# Lights.net
KiCad netlist of a schematic drawn in Altium Designer
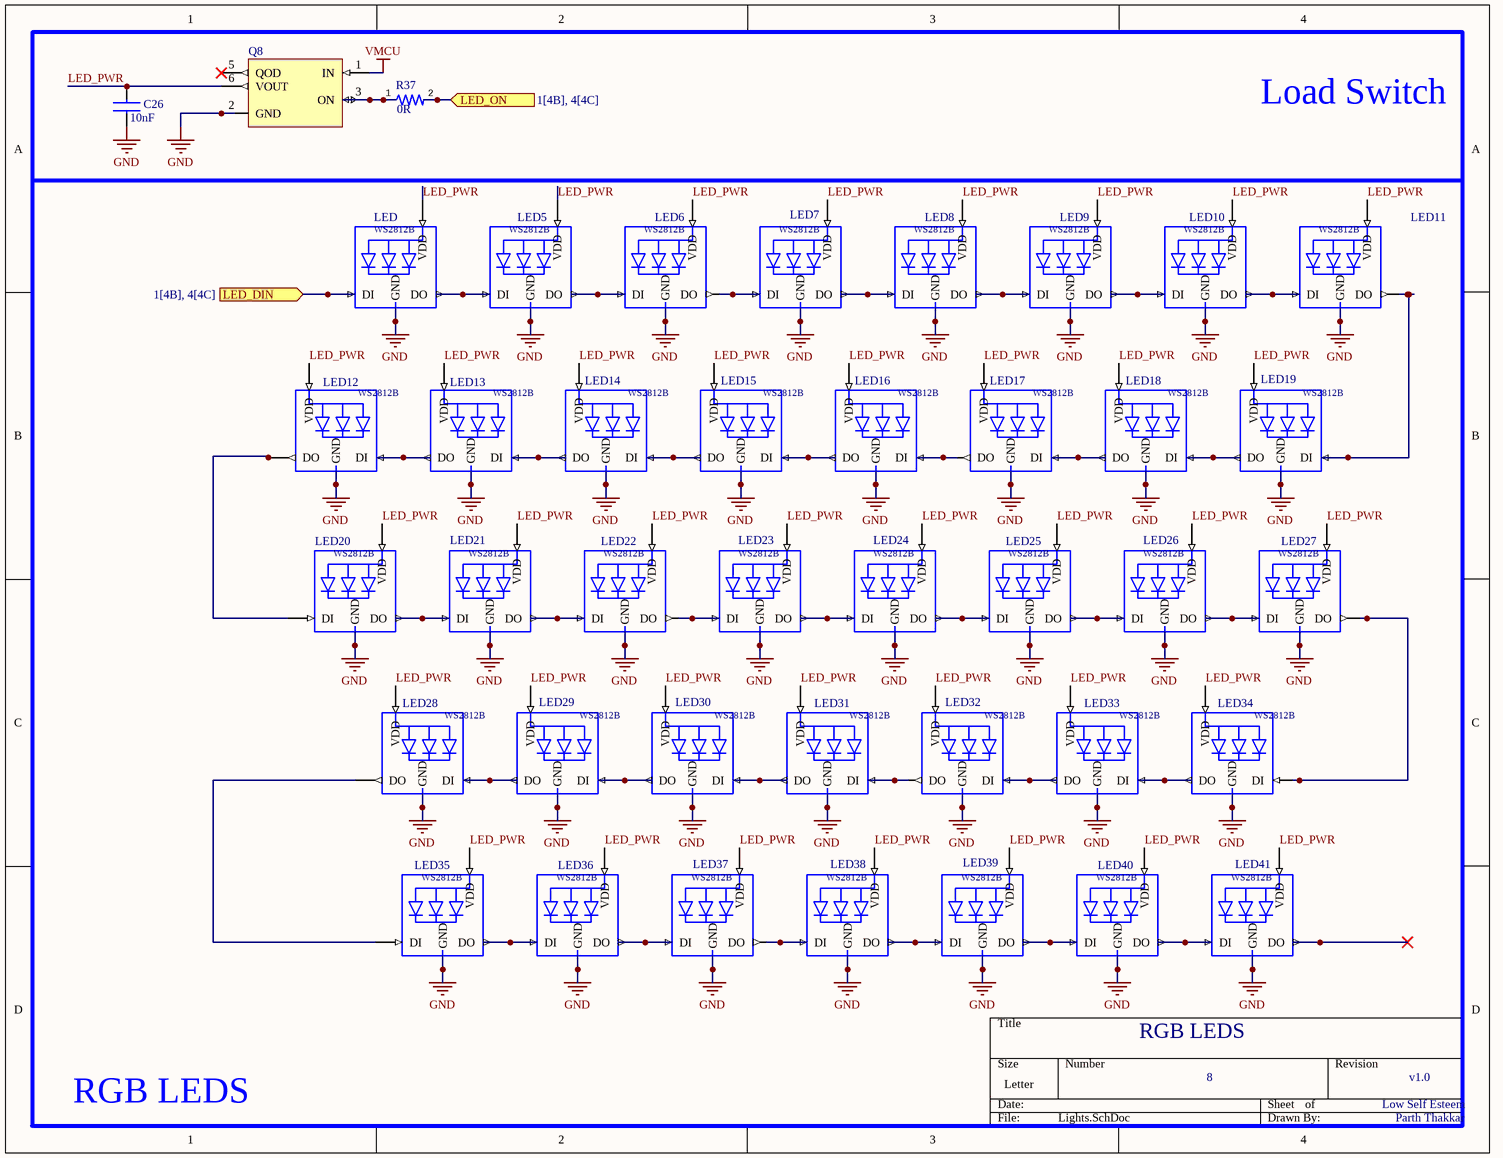
[diagram p0: Lights.SchDoc]

(export (version "E")
  (design (tool "Eeschema 10.0.6"))
  (components
    (comp (ref "C26")
      (value "10nF")
      (footprint "Capacitor 0603")
      (fields
        (field (name "MANUFACTURER") "Murata")
        (field (name "MANUFACTURER PART NUMBER") "GCM188R72A103KA37D")
        (field (name "Comment") "CAP 0.1uF 100V 0603")
      )
      (libsource (lib "InsaneIntegratedLib") (part "CAP 0.1uF 100V 0603"))
    )
    (comp (ref "LED")
      (value "WS2812B")
      (footprint "WS2812B")
      (description "Raspberry Pi HAT _40 pin_ Wheeled Robotics Kit")
      (fields (field (name "MF") "SparkFun Electronics"))
      (libsource (lib "Keyboard_parts") (part "WS2812B"))
    )
    (comp (ref "LED5")
      (value "WS2812B")
      (footprint "WS2812B")
      (description "Raspberry Pi HAT _40 pin_ Wheeled Robotics Kit")
      (fields (field (name "MF") "SparkFun Electronics"))
      (libsource (lib "Keyboard_parts") (part "WS2812B"))
    )
    (comp (ref "LED6")
      (value "WS2812B")
      (footprint "WS2812B")
      (description "Raspberry Pi HAT _40 pin_ Wheeled Robotics Kit")
      (fields (field (name "MF") "SparkFun Electronics"))
      (libsource (lib "Keyboard_parts") (part "WS2812B"))
    )
    (comp (ref "LED7")
      (value "WS2812B")
      (footprint "WS2812B")
      (description "Raspberry Pi HAT _40 pin_ Wheeled Robotics Kit")
      (fields (field (name "MF") "SparkFun Electronics"))
      (libsource (lib "Keyboard_parts") (part "WS2812B"))
    )
    (comp (ref "LED8")
      (value "WS2812B")
      (footprint "WS2812B")
      (description "Raspberry Pi HAT _40 pin_ Wheeled Robotics Kit")
      (fields (field (name "MF") "SparkFun Electronics"))
      (libsource (lib "Keyboard_parts") (part "WS2812B"))
    )
    (comp (ref "LED9")
      (value "WS2812B")
      (footprint "WS2812B")
      (description "Raspberry Pi HAT _40 pin_ Wheeled Robotics Kit")
      (fields (field (name "MF") "SparkFun Electronics"))
      (libsource (lib "Keyboard_parts") (part "WS2812B"))
    )
    (comp (ref "LED10")
      (value "WS2812B")
      (footprint "WS2812B")
      (description "Raspberry Pi HAT _40 pin_ Wheeled Robotics Kit")
      (fields (field (name "MF") "SparkFun Electronics"))
      (libsource (lib "Keyboard_parts") (part "WS2812B"))
    )
    (comp (ref "LED11")
      (value "WS2812B")
      (footprint "WS2812B")
      (description "Raspberry Pi HAT _40 pin_ Wheeled Robotics Kit")
      (fields (field (name "MF") "SparkFun Electronics"))
      (libsource (lib "Keyboard_parts") (part "WS2812B"))
    )
    (comp (ref "LED12")
      (value "WS2812B")
      (footprint "WS2812B")
      (description "Raspberry Pi HAT _40 pin_ Wheeled Robotics Kit")
      (fields (field (name "MF") "SparkFun Electronics"))
      (libsource (lib "Keyboard_parts") (part "WS2812B"))
    )
    (comp (ref "LED13")
      (value "WS2812B")
      (footprint "WS2812B")
      (description "Raspberry Pi HAT _40 pin_ Wheeled Robotics Kit")
      (fields (field (name "MF") "SparkFun Electronics"))
      (libsource (lib "Keyboard_parts") (part "WS2812B"))
    )
    (comp (ref "LED14")
      (value "WS2812B")
      (footprint "WS2812B")
      (description "Raspberry Pi HAT _40 pin_ Wheeled Robotics Kit")
      (fields (field (name "MF") "SparkFun Electronics"))
      (libsource (lib "Keyboard_parts") (part "WS2812B"))
    )
    (comp (ref "LED15")
      (value "WS2812B")
      (footprint "WS2812B")
      (description "Raspberry Pi HAT _40 pin_ Wheeled Robotics Kit")
      (fields (field (name "MF") "SparkFun Electronics"))
      (libsource (lib "Keyboard_parts") (part "WS2812B"))
    )
    (comp (ref "LED16")
      (value "WS2812B")
      (footprint "WS2812B")
      (description "Raspberry Pi HAT _40 pin_ Wheeled Robotics Kit")
      (fields (field (name "MF") "SparkFun Electronics"))
      (libsource (lib "Keyboard_parts") (part "WS2812B"))
    )
    (comp (ref "LED17")
      (value "WS2812B")
      (footprint "WS2812B")
      (description "Raspberry Pi HAT _40 pin_ Wheeled Robotics Kit")
      (fields (field (name "MF") "SparkFun Electronics"))
      (libsource (lib "Keyboard_parts") (part "WS2812B"))
    )
    (comp (ref "LED18")
      (value "WS2812B")
      (footprint "WS2812B")
      (description "Raspberry Pi HAT _40 pin_ Wheeled Robotics Kit")
      (fields (field (name "MF") "SparkFun Electronics"))
      (libsource (lib "Keyboard_parts") (part "WS2812B"))
    )
    (comp (ref "LED19")
      (value "WS2812B")
      (footprint "WS2812B")
      (description "Raspberry Pi HAT _40 pin_ Wheeled Robotics Kit")
      (fields (field (name "MF") "SparkFun Electronics"))
      (libsource (lib "Keyboard_parts") (part "WS2812B"))
    )
    (comp (ref "LED20")
      (value "WS2812B")
      (footprint "WS2812B")
      (description "Raspberry Pi HAT _40 pin_ Wheeled Robotics Kit")
      (fields (field (name "MF") "SparkFun Electronics"))
      (libsource (lib "Keyboard_parts") (part "WS2812B"))
    )
    (comp (ref "LED21")
      (value "WS2812B")
      (footprint "WS2812B")
      (description "Raspberry Pi HAT _40 pin_ Wheeled Robotics Kit")
      (fields (field (name "MF") "SparkFun Electronics"))
      (libsource (lib "Keyboard_parts") (part "WS2812B"))
    )
    (comp (ref "LED22")
      (value "WS2812B")
      (footprint "WS2812B")
      (description "Raspberry Pi HAT _40 pin_ Wheeled Robotics Kit")
      (fields (field (name "MF") "SparkFun Electronics"))
      (libsource (lib "Keyboard_parts") (part "WS2812B"))
    )
    (comp (ref "LED23")
      (value "WS2812B")
      (footprint "WS2812B")
      (description "Raspberry Pi HAT _40 pin_ Wheeled Robotics Kit")
      (fields (field (name "MF") "SparkFun Electronics"))
      (libsource (lib "Keyboard_parts") (part "WS2812B"))
    )
    (comp (ref "LED24")
      (value "WS2812B")
      (footprint "WS2812B")
      (description "Raspberry Pi HAT _40 pin_ Wheeled Robotics Kit")
      (fields (field (name "MF") "SparkFun Electronics"))
      (libsource (lib "Keyboard_parts") (part "WS2812B"))
    )
    (comp (ref "LED25")
      (value "WS2812B")
      (footprint "WS2812B")
      (description "Raspberry Pi HAT _40 pin_ Wheeled Robotics Kit")
      (fields (field (name "MF") "SparkFun Electronics"))
      (libsource (lib "Keyboard_parts") (part "WS2812B"))
    )
    (comp (ref "LED26")
      (value "WS2812B")
      (footprint "WS2812B")
      (description "Raspberry Pi HAT _40 pin_ Wheeled Robotics Kit")
      (fields (field (name "MF") "SparkFun Electronics"))
      (libsource (lib "Keyboard_parts") (part "WS2812B"))
    )
    (comp (ref "LED27")
      (value "WS2812B")
      (footprint "WS2812B")
      (description "Raspberry Pi HAT _40 pin_ Wheeled Robotics Kit")
      (fields (field (name "MF") "SparkFun Electronics"))
      (libsource (lib "Keyboard_parts") (part "WS2812B"))
    )
    (comp (ref "LED28")
      (value "WS2812B")
      (footprint "WS2812B")
      (description "Raspberry Pi HAT _40 pin_ Wheeled Robotics Kit")
      (fields (field (name "MF") "SparkFun Electronics"))
      (libsource (lib "Keyboard_parts") (part "WS2812B"))
    )
    (comp (ref "LED29")
      (value "WS2812B")
      (footprint "WS2812B")
      (description "Raspberry Pi HAT _40 pin_ Wheeled Robotics Kit")
      (fields (field (name "MF") "SparkFun Electronics"))
      (libsource (lib "Keyboard_parts") (part "WS2812B"))
    )
    (comp (ref "LED30")
      (value "WS2812B")
      (footprint "WS2812B")
      (description "Raspberry Pi HAT _40 pin_ Wheeled Robotics Kit")
      (fields (field (name "MF") "SparkFun Electronics"))
      (libsource (lib "Keyboard_parts") (part "WS2812B"))
    )
    (comp (ref "LED31")
      (value "WS2812B")
      (footprint "WS2812B")
      (description "Raspberry Pi HAT _40 pin_ Wheeled Robotics Kit")
      (fields (field (name "MF") "SparkFun Electronics"))
      (libsource (lib "Keyboard_parts") (part "WS2812B"))
    )
    (comp (ref "LED32")
      (value "WS2812B")
      (footprint "WS2812B")
      (description "Raspberry Pi HAT _40 pin_ Wheeled Robotics Kit")
      (fields (field (name "MF") "SparkFun Electronics"))
      (libsource (lib "Keyboard_parts") (part "WS2812B"))
    )
    (comp (ref "LED33")
      (value "WS2812B")
      (footprint "WS2812B")
      (description "Raspberry Pi HAT _40 pin_ Wheeled Robotics Kit")
      (fields (field (name "MF") "SparkFun Electronics"))
      (libsource (lib "Keyboard_parts") (part "WS2812B"))
    )
    (comp (ref "LED34")
      (value "WS2812B")
      (footprint "WS2812B")
      (description "Raspberry Pi HAT _40 pin_ Wheeled Robotics Kit")
      (fields (field (name "MF") "SparkFun Electronics"))
      (libsource (lib "Keyboard_parts") (part "WS2812B"))
    )
    (comp (ref "LED35")
      (value "WS2812B")
      (footprint "WS2812B")
      (description "Raspberry Pi HAT _40 pin_ Wheeled Robotics Kit")
      (fields (field (name "MF") "SparkFun Electronics"))
      (libsource (lib "Keyboard_parts") (part "WS2812B"))
    )
    (comp (ref "LED36")
      (value "WS2812B")
      (footprint "WS2812B")
      (description "Raspberry Pi HAT _40 pin_ Wheeled Robotics Kit")
      (fields (field (name "MF") "SparkFun Electronics"))
      (libsource (lib "Keyboard_parts") (part "WS2812B"))
    )
    (comp (ref "LED37")
      (value "WS2812B")
      (footprint "WS2812B")
      (description "Raspberry Pi HAT _40 pin_ Wheeled Robotics Kit")
      (fields (field (name "MF") "SparkFun Electronics"))
      (libsource (lib "Keyboard_parts") (part "WS2812B"))
    )
    (comp (ref "LED38")
      (value "WS2812B")
      (footprint "WS2812B")
      (description "Raspberry Pi HAT _40 pin_ Wheeled Robotics Kit")
      (fields (field (name "MF") "SparkFun Electronics"))
      (libsource (lib "Keyboard_parts") (part "WS2812B"))
    )
    (comp (ref "LED39")
      (value "WS2812B")
      (footprint "WS2812B")
      (description "Raspberry Pi HAT _40 pin_ Wheeled Robotics Kit")
      (fields (field (name "MF") "SparkFun Electronics"))
      (libsource (lib "Keyboard_parts") (part "WS2812B"))
    )
    (comp (ref "LED40")
      (value "WS2812B")
      (footprint "WS2812B")
      (description "Raspberry Pi HAT _40 pin_ Wheeled Robotics Kit")
      (fields (field (name "MF") "SparkFun Electronics"))
      (libsource (lib "Keyboard_parts") (part "WS2812B"))
    )
    (comp (ref "LED41")
      (value "WS2812B")
      (footprint "WS2812B")
      (description "Raspberry Pi HAT _40 pin_ Wheeled Robotics Kit")
      (fields (field (name "MF") "SparkFun Electronics"))
      (libsource (lib "Keyboard_parts") (part "WS2812B"))
    )
    (comp (ref "Q8")
      (value "TPS22919")
      (footprint "TPS22919DCKR - Load SW")
      (description "Buffer/Inverter Based Peripheral Driver, 3A, PDSO6")
      (fields
        (field (name "MANUFACTURER") "Texas Instruments")
        (field (name "MANUFACTURER PART NUMBER") "TPS22919DCKT")
      )
      (libsource (lib "Keyboard_parts") (part "TPS22919"))
    )
    (comp (ref "R37")
      (value "0R")
      (footprint "Resistor 0402")
      (description "Metal Glaze/thick Film, 0.0625W, 0ohm, Surface Mount, 0402")
      (fields
        (field (name "MANUFACTURER") "Yageo")
        (field (name "MANUFACTURER PART NUMBER") "RC0402JR-070RL")
      )
      (libsource (lib "InsaneIntegratedLib") (part "RES 0R 0402"))
    )
  )
  (nets
    (net (code "2") (name "/LED_DIN") (class "Default")
      (node (ref "LED") (pin "4-DIN") (pinfunction "DI_4-DIN") (pintype "input"))
    )
    (net (code "3") (name "/LED_ON") (class "Default")
      (node (ref "R37") (pin "2") (pinfunction "2_2") (pintype "passive"))
    )
    (net (code "4") (name "/LED_PWR") (class "Default")
      (node (ref "C26") (pin "2") (pinfunction "2_2") (pintype "passive"))
      (node (ref "LED") (pin "1-VDD") (pinfunction "VDD_1-VDD") (pintype "input"))
      (node (ref "LED10") (pin "1-VDD") (pinfunction "VDD_1-VDD") (pintype "input"))
      (node (ref "LED11") (pin "1-VDD") (pinfunction "VDD_1-VDD") (pintype "input"))
      (node (ref "LED12") (pin "1-VDD") (pinfunction "VDD_1-VDD") (pintype "input"))
      (node (ref "LED13") (pin "1-VDD") (pinfunction "VDD_1-VDD") (pintype "input"))
      (node (ref "LED14") (pin "1-VDD") (pinfunction "VDD_1-VDD") (pintype "input"))
      (node (ref "LED15") (pin "1-VDD") (pinfunction "VDD_1-VDD") (pintype "input"))
      (node (ref "LED16") (pin "1-VDD") (pinfunction "VDD_1-VDD") (pintype "input"))
      (node (ref "LED17") (pin "1-VDD") (pinfunction "VDD_1-VDD") (pintype "input"))
      (node (ref "LED18") (pin "1-VDD") (pinfunction "VDD_1-VDD") (pintype "input"))
      (node (ref "LED19") (pin "1-VDD") (pinfunction "VDD_1-VDD") (pintype "input"))
      (node (ref "LED20") (pin "1-VDD") (pinfunction "VDD_1-VDD") (pintype "input"))
      (node (ref "LED21") (pin "1-VDD") (pinfunction "VDD_1-VDD") (pintype "input"))
      (node (ref "LED22") (pin "1-VDD") (pinfunction "VDD_1-VDD") (pintype "input"))
      (node (ref "LED23") (pin "1-VDD") (pinfunction "VDD_1-VDD") (pintype "input"))
      (node (ref "LED24") (pin "1-VDD") (pinfunction "VDD_1-VDD") (pintype "input"))
      (node (ref "LED25") (pin "1-VDD") (pinfunction "VDD_1-VDD") (pintype "input"))
      (node (ref "LED26") (pin "1-VDD") (pinfunction "VDD_1-VDD") (pintype "input"))
      (node (ref "LED27") (pin "1-VDD") (pinfunction "VDD_1-VDD") (pintype "input"))
      (node (ref "LED28") (pin "1-VDD") (pinfunction "VDD_1-VDD") (pintype "input"))
      (node (ref "LED29") (pin "1-VDD") (pinfunction "VDD_1-VDD") (pintype "input"))
      (node (ref "LED30") (pin "1-VDD") (pinfunction "VDD_1-VDD") (pintype "input"))
      (node (ref "LED31") (pin "1-VDD") (pinfunction "VDD_1-VDD") (pintype "input"))
      (node (ref "LED32") (pin "1-VDD") (pinfunction "VDD_1-VDD") (pintype "input"))
      (node (ref "LED33") (pin "1-VDD") (pinfunction "VDD_1-VDD") (pintype "input"))
      (node (ref "LED34") (pin "1-VDD") (pinfunction "VDD_1-VDD") (pintype "input"))
      (node (ref "LED35") (pin "1-VDD") (pinfunction "VDD_1-VDD") (pintype "input"))
      (node (ref "LED36") (pin "1-VDD") (pinfunction "VDD_1-VDD") (pintype "input"))
      (node (ref "LED37") (pin "1-VDD") (pinfunction "VDD_1-VDD") (pintype "input"))
      (node (ref "LED38") (pin "1-VDD") (pinfunction "VDD_1-VDD") (pintype "input"))
      (node (ref "LED39") (pin "1-VDD") (pinfunction "VDD_1-VDD") (pintype "input"))
      (node (ref "LED40") (pin "1-VDD") (pinfunction "VDD_1-VDD") (pintype "input"))
      (node (ref "LED41") (pin "1-VDD") (pinfunction "VDD_1-VDD") (pintype "input"))
      (node (ref "LED5") (pin "1-VDD") (pinfunction "VDD_1-VDD") (pintype "input"))
      (node (ref "LED6") (pin "1-VDD") (pinfunction "VDD_1-VDD") (pintype "input"))
      (node (ref "LED7") (pin "1-VDD") (pinfunction "VDD_1-VDD") (pintype "input"))
      (node (ref "LED8") (pin "1-VDD") (pinfunction "VDD_1-VDD") (pintype "input"))
      (node (ref "LED9") (pin "1-VDD") (pinfunction "VDD_1-VDD") (pintype "input"))
      (node (ref "Q8") (pin "6") (pinfunction "VOUT_6") (pintype "output"))
    )
    (net (code "5") (name "GND") (class "Default")
      (node (ref "C26") (pin "1") (pinfunction "1_1") (pintype "passive"))
      (node (ref "LED") (pin "3-GND") (pinfunction "GND_3-GND") (pintype "power_in"))
      (node (ref "LED10") (pin "3-GND") (pinfunction "GND_3-GND") (pintype "power_in"))
      (node (ref "LED11") (pin "3-GND") (pinfunction "GND_3-GND") (pintype "power_in"))
      (node (ref "LED12") (pin "3-GND") (pinfunction "GND_3-GND") (pintype "power_in"))
      (node (ref "LED13") (pin "3-GND") (pinfunction "GND_3-GND") (pintype "power_in"))
      (node (ref "LED14") (pin "3-GND") (pinfunction "GND_3-GND") (pintype "power_in"))
      (node (ref "LED15") (pin "3-GND") (pinfunction "GND_3-GND") (pintype "power_in"))
      (node (ref "LED16") (pin "3-GND") (pinfunction "GND_3-GND") (pintype "power_in"))
      (node (ref "LED17") (pin "3-GND") (pinfunction "GND_3-GND") (pintype "power_in"))
      (node (ref "LED18") (pin "3-GND") (pinfunction "GND_3-GND") (pintype "power_in"))
      (node (ref "LED19") (pin "3-GND") (pinfunction "GND_3-GND") (pintype "power_in"))
      (node (ref "LED20") (pin "3-GND") (pinfunction "GND_3-GND") (pintype "power_in"))
      (node (ref "LED21") (pin "3-GND") (pinfunction "GND_3-GND") (pintype "power_in"))
      (node (ref "LED22") (pin "3-GND") (pinfunction "GND_3-GND") (pintype "power_in"))
      (node (ref "LED23") (pin "3-GND") (pinfunction "GND_3-GND") (pintype "power_in"))
      (node (ref "LED24") (pin "3-GND") (pinfunction "GND_3-GND") (pintype "power_in"))
      (node (ref "LED25") (pin "3-GND") (pinfunction "GND_3-GND") (pintype "power_in"))
      (node (ref "LED26") (pin "3-GND") (pinfunction "GND_3-GND") (pintype "power_in"))
      (node (ref "LED27") (pin "3-GND") (pinfunction "GND_3-GND") (pintype "power_in"))
      (node (ref "LED28") (pin "3-GND") (pinfunction "GND_3-GND") (pintype "power_in"))
      (node (ref "LED29") (pin "3-GND") (pinfunction "GND_3-GND") (pintype "power_in"))
      (node (ref "LED30") (pin "3-GND") (pinfunction "GND_3-GND") (pintype "power_in"))
      (node (ref "LED31") (pin "3-GND") (pinfunction "GND_3-GND") (pintype "power_in"))
      (node (ref "LED32") (pin "3-GND") (pinfunction "GND_3-GND") (pintype "power_in"))
      (node (ref "LED33") (pin "3-GND") (pinfunction "GND_3-GND") (pintype "power_in"))
      (node (ref "LED34") (pin "3-GND") (pinfunction "GND_3-GND") (pintype "power_in"))
      (node (ref "LED35") (pin "3-GND") (pinfunction "GND_3-GND") (pintype "power_in"))
      (node (ref "LED36") (pin "3-GND") (pinfunction "GND_3-GND") (pintype "power_in"))
      (node (ref "LED37") (pin "3-GND") (pinfunction "GND_3-GND") (pintype "power_in"))
      (node (ref "LED38") (pin "3-GND") (pinfunction "GND_3-GND") (pintype "power_in"))
      (node (ref "LED39") (pin "3-GND") (pinfunction "GND_3-GND") (pintype "power_in"))
      (node (ref "LED40") (pin "3-GND") (pinfunction "GND_3-GND") (pintype "power_in"))
      (node (ref "LED41") (pin "3-GND") (pinfunction "GND_3-GND") (pintype "power_in"))
      (node (ref "LED5") (pin "3-GND") (pinfunction "GND_3-GND") (pintype "power_in"))
      (node (ref "LED6") (pin "3-GND") (pinfunction "GND_3-GND") (pintype "power_in"))
      (node (ref "LED7") (pin "3-GND") (pinfunction "GND_3-GND") (pintype "power_in"))
      (node (ref "LED8") (pin "3-GND") (pinfunction "GND_3-GND") (pintype "power_in"))
      (node (ref "LED9") (pin "3-GND") (pinfunction "GND_3-GND") (pintype "power_in"))
      (node (ref "Q8") (pin "2") (pinfunction "GND_2") (pintype "passive"))
    )
    (net (code "6") (name "Net-(LED-DO)") (class "Default")
      (node (ref "LED") (pin "2-DOUT") (pinfunction "DO_2-DOUT") (pintype "output"))
      (node (ref "LED5") (pin "4-DIN") (pinfunction "DI_4-DIN") (pintype "input"))
    )
    (net (code "7") (name "Net-(LED5-DO)") (class "Default")
      (node (ref "LED5") (pin "2-DOUT") (pinfunction "DO_2-DOUT") (pintype "output"))
      (node (ref "LED6") (pin "4-DIN") (pinfunction "DI_4-DIN") (pintype "input"))
    )
    (net (code "8") (name "Net-(LED6-DO)") (class "Default")
      (node (ref "LED6") (pin "2-DOUT") (pinfunction "DO_2-DOUT") (pintype "output"))
      (node (ref "LED7") (pin "4-DIN") (pinfunction "DI_4-DIN") (pintype "input"))
    )
    (net (code "9") (name "Net-(LED7-DO)") (class "Default")
      (node (ref "LED7") (pin "2-DOUT") (pinfunction "DO_2-DOUT") (pintype "output"))
      (node (ref "LED8") (pin "4-DIN") (pinfunction "DI_4-DIN") (pintype "input"))
    )
    (net (code "10") (name "Net-(LED8-DO)") (class "Default")
      (node (ref "LED8") (pin "2-DOUT") (pinfunction "DO_2-DOUT") (pintype "output"))
      (node (ref "LED9") (pin "4-DIN") (pinfunction "DI_4-DIN") (pintype "input"))
    )
    (net (code "11") (name "Net-(LED10-DI)") (class "Default")
      (node (ref "LED10") (pin "4-DIN") (pinfunction "DI_4-DIN") (pintype "input"))
      (node (ref "LED9") (pin "2-DOUT") (pinfunction "DO_2-DOUT") (pintype "output"))
    )
    (net (code "12") (name "Net-(LED10-DO)") (class "Default")
      (node (ref "LED10") (pin "2-DOUT") (pinfunction "DO_2-DOUT") (pintype "output"))
      (node (ref "LED11") (pin "4-DIN") (pinfunction "DI_4-DIN") (pintype "input"))
    )
    (net (code "13") (name "Net-(LED11-DO)") (class "Default")
      (node (ref "LED11") (pin "2-DOUT") (pinfunction "DO_2-DOUT") (pintype "output"))
      (node (ref "LED19") (pin "4-DIN") (pinfunction "DI_4-DIN") (pintype "input"))
    )
    (net (code "14") (name "Net-(LED12-DI)") (class "Default")
      (node (ref "LED12") (pin "4-DIN") (pinfunction "DI_4-DIN") (pintype "input"))
      (node (ref "LED13") (pin "2-DOUT") (pinfunction "DO_2-DOUT") (pintype "output"))
    )
    (net (code "15") (name "Net-(LED12-DO)") (class "Default")
      (node (ref "LED12") (pin "2-DOUT") (pinfunction "DO_2-DOUT") (pintype "output"))
      (node (ref "LED20") (pin "4-DIN") (pinfunction "DI_4-DIN") (pintype "input"))
    )
    (net (code "16") (name "Net-(LED13-DI)") (class "Default")
      (node (ref "LED13") (pin "4-DIN") (pinfunction "DI_4-DIN") (pintype "input"))
      (node (ref "LED14") (pin "2-DOUT") (pinfunction "DO_2-DOUT") (pintype "output"))
    )
    (net (code "17") (name "Net-(LED14-DI)") (class "Default")
      (node (ref "LED14") (pin "4-DIN") (pinfunction "DI_4-DIN") (pintype "input"))
      (node (ref "LED15") (pin "2-DOUT") (pinfunction "DO_2-DOUT") (pintype "output"))
    )
    (net (code "18") (name "Net-(LED15-DI)") (class "Default")
      (node (ref "LED15") (pin "4-DIN") (pinfunction "DI_4-DIN") (pintype "input"))
      (node (ref "LED16") (pin "2-DOUT") (pinfunction "DO_2-DOUT") (pintype "output"))
    )
    (net (code "19") (name "Net-(LED16-DI)") (class "Default")
      (node (ref "LED16") (pin "4-DIN") (pinfunction "DI_4-DIN") (pintype "input"))
      (node (ref "LED17") (pin "2-DOUT") (pinfunction "DO_2-DOUT") (pintype "output"))
    )
    (net (code "20") (name "Net-(LED17-DI)") (class "Default")
      (node (ref "LED17") (pin "4-DIN") (pinfunction "DI_4-DIN") (pintype "input"))
      (node (ref "LED18") (pin "2-DOUT") (pinfunction "DO_2-DOUT") (pintype "output"))
    )
    (net (code "21") (name "Net-(LED18-DI)") (class "Default")
      (node (ref "LED18") (pin "4-DIN") (pinfunction "DI_4-DIN") (pintype "input"))
      (node (ref "LED19") (pin "2-DOUT") (pinfunction "DO_2-DOUT") (pintype "output"))
    )
    (net (code "22") (name "Net-(LED20-DO)") (class "Default")
      (node (ref "LED20") (pin "2-DOUT") (pinfunction "DO_2-DOUT") (pintype "output"))
      (node (ref "LED21") (pin "4-DIN") (pinfunction "DI_4-DIN") (pintype "input"))
    )
    (net (code "23") (name "Net-(LED21-DO)") (class "Default")
      (node (ref "LED21") (pin "2-DOUT") (pinfunction "DO_2-DOUT") (pintype "output"))
      (node (ref "LED22") (pin "4-DIN") (pinfunction "DI_4-DIN") (pintype "input"))
    )
    (net (code "24") (name "Net-(LED22-DO)") (class "Default")
      (node (ref "LED22") (pin "2-DOUT") (pinfunction "DO_2-DOUT") (pintype "output"))
      (node (ref "LED23") (pin "4-DIN") (pinfunction "DI_4-DIN") (pintype "input"))
    )
    (net (code "25") (name "Net-(LED23-DO)") (class "Default")
      (node (ref "LED23") (pin "2-DOUT") (pinfunction "DO_2-DOUT") (pintype "output"))
      (node (ref "LED24") (pin "4-DIN") (pinfunction "DI_4-DIN") (pintype "input"))
    )
    (net (code "26") (name "Net-(LED24-DO)") (class "Default")
      (node (ref "LED24") (pin "2-DOUT") (pinfunction "DO_2-DOUT") (pintype "output"))
      (node (ref "LED25") (pin "4-DIN") (pinfunction "DI_4-DIN") (pintype "input"))
    )
    (net (code "27") (name "Net-(LED25-DO)") (class "Default")
      (node (ref "LED25") (pin "2-DOUT") (pinfunction "DO_2-DOUT") (pintype "output"))
      (node (ref "LED26") (pin "4-DIN") (pinfunction "DI_4-DIN") (pintype "input"))
    )
    (net (code "28") (name "Net-(LED26-DO)") (class "Default")
      (node (ref "LED26") (pin "2-DOUT") (pinfunction "DO_2-DOUT") (pintype "output"))
      (node (ref "LED27") (pin "4-DIN") (pinfunction "DI_4-DIN") (pintype "input"))
    )
    (net (code "29") (name "Net-(LED27-DO)") (class "Default")
      (node (ref "LED27") (pin "2-DOUT") (pinfunction "DO_2-DOUT") (pintype "output"))
      (node (ref "LED34") (pin "4-DIN") (pinfunction "DI_4-DIN") (pintype "input"))
    )
    (net (code "30") (name "Net-(LED28-DI)") (class "Default")
      (node (ref "LED28") (pin "4-DIN") (pinfunction "DI_4-DIN") (pintype "input"))
      (node (ref "LED29") (pin "2-DOUT") (pinfunction "DO_2-DOUT") (pintype "output"))
    )
    (net (code "31") (name "Net-(LED28-DO)") (class "Default")
      (node (ref "LED28") (pin "2-DOUT") (pinfunction "DO_2-DOUT") (pintype "output"))
      (node (ref "LED35") (pin "4-DIN") (pinfunction "DI_4-DIN") (pintype "input"))
    )
    (net (code "32") (name "Net-(LED29-DI)") (class "Default")
      (node (ref "LED29") (pin "4-DIN") (pinfunction "DI_4-DIN") (pintype "input"))
      (node (ref "LED30") (pin "2-DOUT") (pinfunction "DO_2-DOUT") (pintype "output"))
    )
    (net (code "33") (name "Net-(LED30-DI)") (class "Default")
      (node (ref "LED30") (pin "4-DIN") (pinfunction "DI_4-DIN") (pintype "input"))
      (node (ref "LED31") (pin "2-DOUT") (pinfunction "DO_2-DOUT") (pintype "output"))
    )
    (net (code "34") (name "Net-(LED31-DI)") (class "Default")
      (node (ref "LED31") (pin "4-DIN") (pinfunction "DI_4-DIN") (pintype "input"))
      (node (ref "LED32") (pin "2-DOUT") (pinfunction "DO_2-DOUT") (pintype "output"))
    )
    (net (code "35") (name "Net-(LED32-DI)") (class "Default")
      (node (ref "LED32") (pin "4-DIN") (pinfunction "DI_4-DIN") (pintype "input"))
      (node (ref "LED33") (pin "2-DOUT") (pinfunction "DO_2-DOUT") (pintype "output"))
    )
    (net (code "36") (name "Net-(LED33-DI)") (class "Default")
      (node (ref "LED33") (pin "4-DIN") (pinfunction "DI_4-DIN") (pintype "input"))
      (node (ref "LED34") (pin "2-DOUT") (pinfunction "DO_2-DOUT") (pintype "output"))
    )
    (net (code "37") (name "Net-(LED35-DO)") (class "Default")
      (node (ref "LED35") (pin "2-DOUT") (pinfunction "DO_2-DOUT") (pintype "output"))
      (node (ref "LED36") (pin "4-DIN") (pinfunction "DI_4-DIN") (pintype "input"))
    )
    (net (code "38") (name "Net-(LED36-DO)") (class "Default")
      (node (ref "LED36") (pin "2-DOUT") (pinfunction "DO_2-DOUT") (pintype "output"))
      (node (ref "LED37") (pin "4-DIN") (pinfunction "DI_4-DIN") (pintype "input"))
    )
    (net (code "39") (name "Net-(LED37-DO)") (class "Default")
      (node (ref "LED37") (pin "2-DOUT") (pinfunction "DO_2-DOUT") (pintype "output"))
      (node (ref "LED38") (pin "4-DIN") (pinfunction "DI_4-DIN") (pintype "input"))
    )
    (net (code "40") (name "Net-(LED38-DO)") (class "Default")
      (node (ref "LED38") (pin "2-DOUT") (pinfunction "DO_2-DOUT") (pintype "output"))
      (node (ref "LED39") (pin "4-DIN") (pinfunction "DI_4-DIN") (pintype "input"))
    )
    (net (code "41") (name "Net-(LED39-DO)") (class "Default")
      (node (ref "LED39") (pin "2-DOUT") (pinfunction "DO_2-DOUT") (pintype "output"))
      (node (ref "LED40") (pin "4-DIN") (pinfunction "DI_4-DIN") (pintype "input"))
    )
    (net (code "42") (name "Net-(LED40-DO)") (class "Default")
      (node (ref "LED40") (pin "2-DOUT") (pinfunction "DO_2-DOUT") (pintype "output"))
      (node (ref "LED41") (pin "4-DIN") (pinfunction "DI_4-DIN") (pintype "input"))
    )
    (net (code "43") (name "Net-(Q8-ON)") (class "Default")
      (node (ref "Q8") (pin "3") (pinfunction "ON_3") (pintype "bidirectional"))
      (node (ref "R37") (pin "1") (pinfunction "1_1") (pintype "passive"))
    )
    (net (code "44") (name "VMCU") (class "Default")
      (node (ref "Q8") (pin "1") (pinfunction "IN_1") (pintype "input"))
    )
    (net (code "45") (name "unconnected-(LED41-DO-Pad2-DOUT)") (class "Default")
      (node (ref "LED41") (pin "2-DOUT") (pinfunction "DO_2-DOUT") (pintype "output+no_connect"))
    )
    (net (code "46") (name "unconnected-(Q8-QOD-Pad5)") (class "Default")
      (node (ref "Q8") (pin "5") (pinfunction "QOD_5") (pintype "output+no_connect"))
    )
  )
)
